# M901X.net
KiCad netlist of a schematic drawn in EAGLE
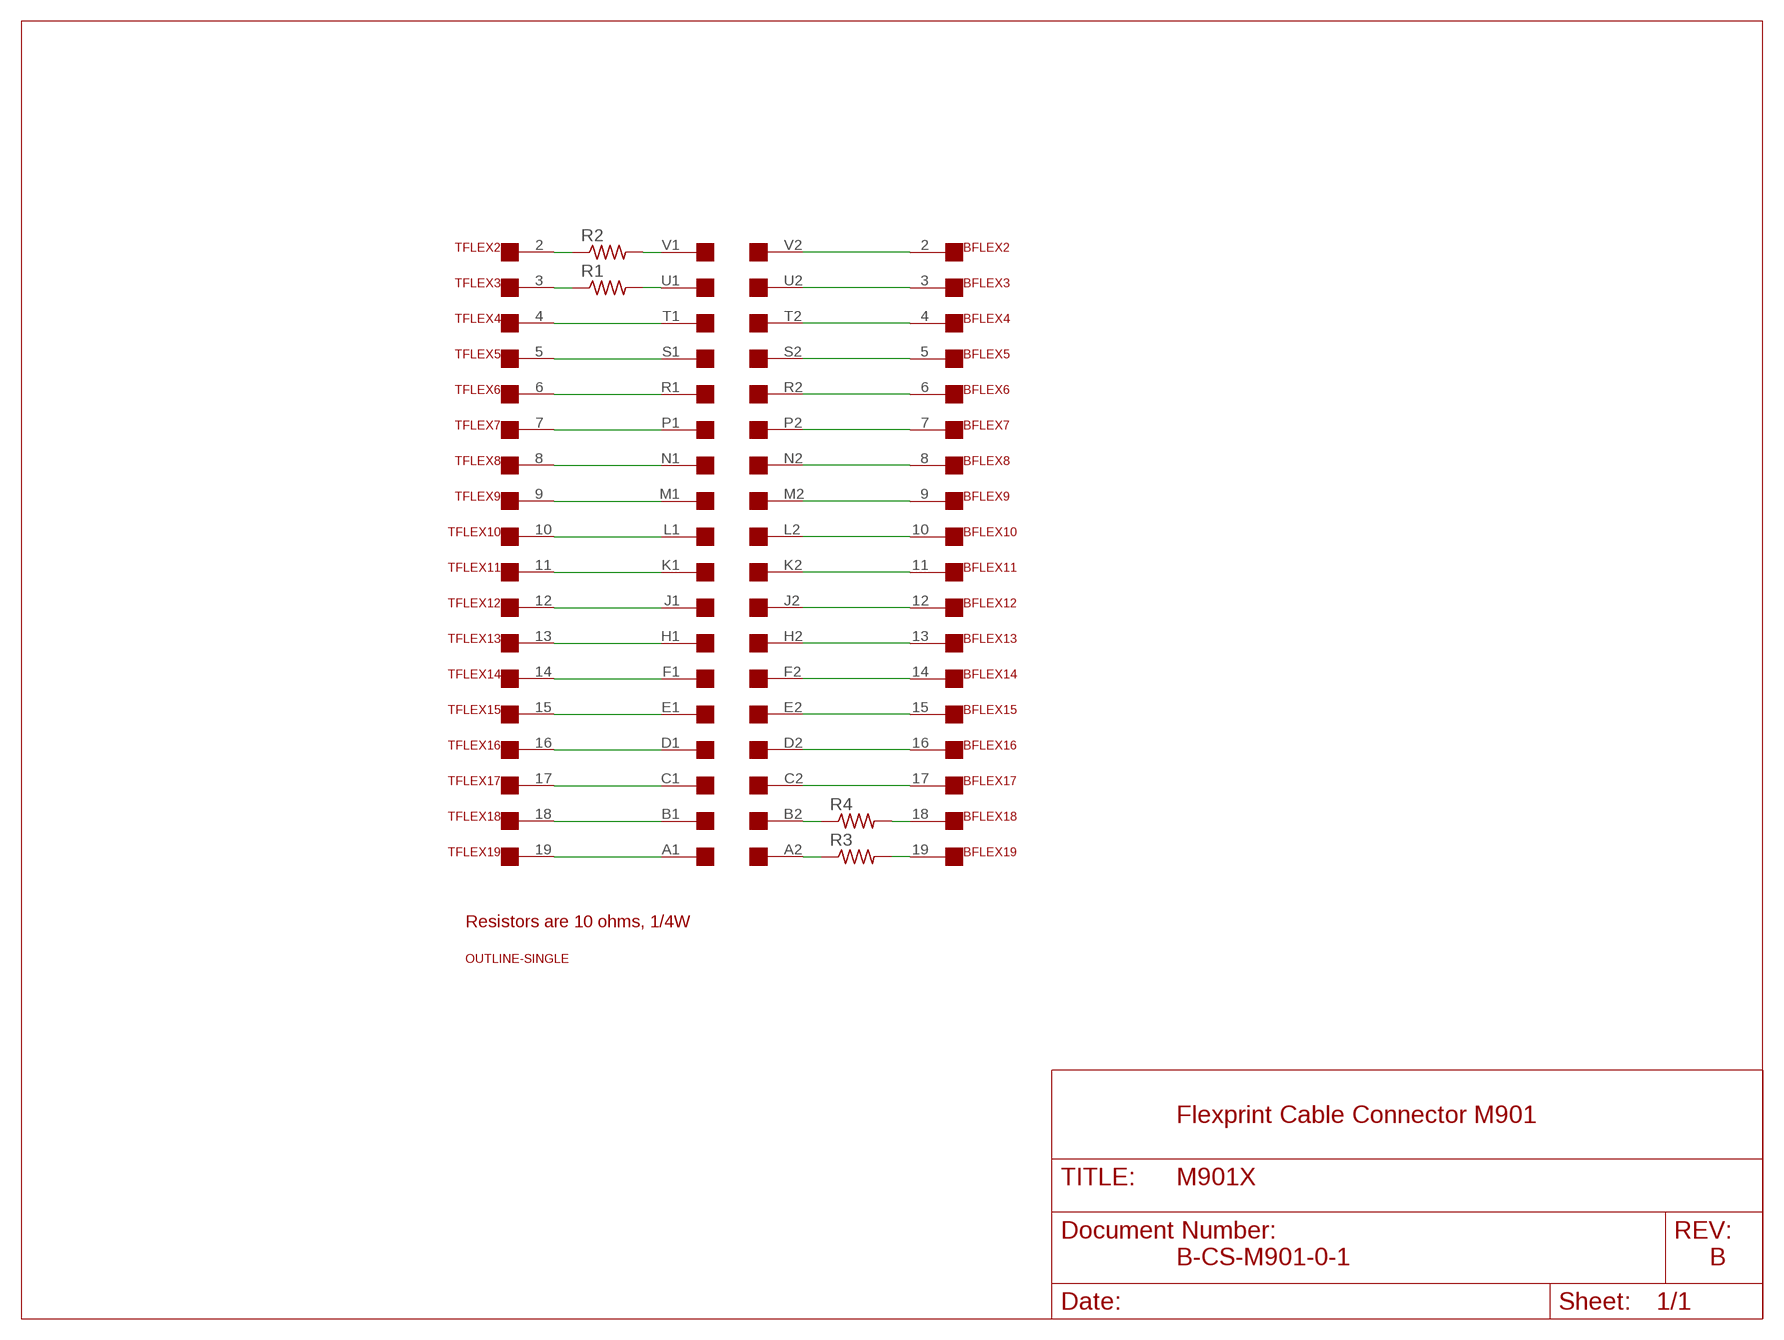
[diagram p0: schematic, sheet 1]

(export (version "E")
  (design (tool "Eeschema 10.0.6"))
  (components
    (comp (ref "BFLEX")
      (value "FLEX19")
      (footprint "eagle-import:FLEX19")
      (libsource (lib "eagle-import") (part "FLEX19"))
    )
    (comp (ref "R1")
      (value "R-US_0207/10")
      (footprint "eagle-import:0207_10")
      (libsource (lib "eagle-import") (part "R-US_0207/10"))
    )
    (comp (ref "R2")
      (value "R-US_0207/10")
      (footprint "eagle-import:0207_10")
      (libsource (lib "eagle-import") (part "R-US_0207/10"))
    )
    (comp (ref "R3")
      (value "R-US_0207/10")
      (footprint "eagle-import:0207_10")
      (libsource (lib "eagle-import") (part "R-US_0207/10"))
    )
    (comp (ref "R4")
      (value "R-US_0207/10")
      (footprint "eagle-import:0207_10")
      (libsource (lib "eagle-import") (part "R-US_0207/10"))
    )
    (comp (ref "TFLEX")
      (value "FLEX19")
      (footprint "eagle-import:FLEX19")
      (libsource (lib "eagle-import") (part "FLEX19"))
    )
    (comp (ref "U$1")
      (value "SINGLE")
      (footprint "eagle-import:EDGE-CON2")
      (libsource (lib "eagle-import") (part "SINGLE"))
    )
    (comp (ref "U$2")
      (value "OUTLINE-SINGLE")
      (footprint "eagle-import:SINGLE")
      (libsource (lib "eagle-import") (part "OUTLINE-SINGLE"))
    )
  )
  (nets
    (net (code "1") (name "Net-(BFLEXB-1)") (class "Default")
      (node (ref "BFLEX") (pin "10") (pinfunction "1_10") (pintype "passive"))
      (node (ref "U$1") (pin "L2") (pinfunction "1_L2") (pintype "bidirectional"))
    )
    (net (code "2") (name "Net-(BFLEXC-1)") (class "Default")
      (node (ref "BFLEX") (pin "11") (pinfunction "1_11") (pintype "passive"))
      (node (ref "U$1") (pin "K2") (pinfunction "1_K2") (pintype "bidirectional"))
    )
    (net (code "3") (name "Net-(BFLEXD-1)") (class "Default")
      (node (ref "BFLEX") (pin "12") (pinfunction "1_12") (pintype "passive"))
      (node (ref "U$1") (pin "J2") (pinfunction "1_J2") (pintype "bidirectional"))
    )
    (net (code "4") (name "Net-(BFLEXE-1)") (class "Default")
      (node (ref "BFLEX") (pin "13") (pinfunction "1_13") (pintype "passive"))
      (node (ref "U$1") (pin "H2") (pinfunction "1_H2") (pintype "bidirectional"))
    )
    (net (code "5") (name "Net-(BFLEXF-1)") (class "Default")
      (node (ref "BFLEX") (pin "14") (pinfunction "1_14") (pintype "passive"))
      (node (ref "U$1") (pin "F2") (pinfunction "1_F2") (pintype "bidirectional"))
    )
    (net (code "6") (name "Net-(BFLEXG-1)") (class "Default")
      (node (ref "BFLEX") (pin "15") (pinfunction "1_15") (pintype "passive"))
      (node (ref "U$1") (pin "E2") (pinfunction "1_E2") (pintype "bidirectional"))
    )
    (net (code "7") (name "Net-(BFLEXH-1)") (class "Default")
      (node (ref "BFLEX") (pin "16") (pinfunction "1_16") (pintype "passive"))
      (node (ref "U$1") (pin "D2") (pinfunction "1_D2") (pintype "bidirectional"))
    )
    (net (code "8") (name "Net-(BFLEXI-1)") (class "Default")
      (node (ref "BFLEX") (pin "17") (pinfunction "1_17") (pintype "passive"))
      (node (ref "U$1") (pin "C2") (pinfunction "1_C2") (pintype "bidirectional"))
    )
    (net (code "9") (name "Net-(BFLEXJ-1)") (class "Default")
      (node (ref "BFLEX") (pin "18") (pinfunction "1_18") (pintype "passive"))
      (node (ref "R4") (pin "2") (pinfunction "2_2") (pintype "passive"))
    )
    (net (code "10") (name "Net-(BFLEXK-1)") (class "Default")
      (node (ref "BFLEX") (pin "19") (pinfunction "1_19") (pintype "passive"))
      (node (ref "R3") (pin "2") (pinfunction "2_2") (pintype "passive"))
    )
    (net (code "11") (name "Net-(BFLEXL-1)") (class "Default")
      (node (ref "BFLEX") (pin "2") (pinfunction "1_2") (pintype "passive"))
      (node (ref "U$1") (pin "V2") (pinfunction "1_V2") (pintype "bidirectional"))
    )
    (net (code "12") (name "Net-(BFLEXM-1)") (class "Default")
      (node (ref "BFLEX") (pin "3") (pinfunction "1_3") (pintype "passive"))
      (node (ref "U$1") (pin "U2") (pinfunction "1_U2") (pintype "bidirectional"))
    )
    (net (code "13") (name "Net-(BFLEXN-1)") (class "Default")
      (node (ref "BFLEX") (pin "4") (pinfunction "1_4") (pintype "passive"))
      (node (ref "U$1") (pin "T2") (pinfunction "1_T2") (pintype "bidirectional"))
    )
    (net (code "14") (name "Net-(BFLEXO-1)") (class "Default")
      (node (ref "BFLEX") (pin "5") (pinfunction "1_5") (pintype "passive"))
      (node (ref "U$1") (pin "S2") (pinfunction "1_S2") (pintype "bidirectional"))
    )
    (net (code "15") (name "Net-(BFLEXP-1)") (class "Default")
      (node (ref "BFLEX") (pin "6") (pinfunction "1_6") (pintype "passive"))
      (node (ref "U$1") (pin "R2") (pinfunction "1_R2") (pintype "bidirectional"))
    )
    (net (code "16") (name "Net-(BFLEXQ-1)") (class "Default")
      (node (ref "BFLEX") (pin "7") (pinfunction "1_7") (pintype "passive"))
      (node (ref "U$1") (pin "P2") (pinfunction "1_P2") (pintype "bidirectional"))
    )
    (net (code "17") (name "Net-(BFLEXR-1)") (class "Default")
      (node (ref "BFLEX") (pin "8") (pinfunction "1_8") (pintype "passive"))
      (node (ref "U$1") (pin "N2") (pinfunction "1_N2") (pintype "bidirectional"))
    )
    (net (code "18") (name "Net-(BFLEXS-1)") (class "Default")
      (node (ref "BFLEX") (pin "9") (pinfunction "1_9") (pintype "passive"))
      (node (ref "U$1") (pin "M2") (pinfunction "1_M2") (pintype "bidirectional"))
    )
    (net (code "19") (name "Net-(TFLEXB-1)") (class "Default")
      (node (ref "TFLEX") (pin "10") (pinfunction "1_10") (pintype "passive"))
      (node (ref "U$1") (pin "L1") (pinfunction "1_L1") (pintype "bidirectional"))
    )
    (net (code "20") (name "Net-(TFLEXC-1)") (class "Default")
      (node (ref "TFLEX") (pin "11") (pinfunction "1_11") (pintype "passive"))
      (node (ref "U$1") (pin "K1") (pinfunction "1_K1") (pintype "bidirectional"))
    )
    (net (code "21") (name "Net-(TFLEXD-1)") (class "Default")
      (node (ref "TFLEX") (pin "12") (pinfunction "1_12") (pintype "passive"))
      (node (ref "U$1") (pin "J1") (pinfunction "1_J1") (pintype "bidirectional"))
    )
    (net (code "22") (name "Net-(TFLEXE-1)") (class "Default")
      (node (ref "TFLEX") (pin "13") (pinfunction "1_13") (pintype "passive"))
      (node (ref "U$1") (pin "H1") (pinfunction "1_H1") (pintype "bidirectional"))
    )
    (net (code "23") (name "Net-(TFLEXF-1)") (class "Default")
      (node (ref "TFLEX") (pin "14") (pinfunction "1_14") (pintype "passive"))
      (node (ref "U$1") (pin "F1") (pinfunction "1_F1") (pintype "bidirectional"))
    )
    (net (code "24") (name "Net-(TFLEXG-1)") (class "Default")
      (node (ref "TFLEX") (pin "15") (pinfunction "1_15") (pintype "passive"))
      (node (ref "U$1") (pin "E1") (pinfunction "1_E1") (pintype "bidirectional"))
    )
    (net (code "25") (name "Net-(TFLEXH-1)") (class "Default")
      (node (ref "TFLEX") (pin "16") (pinfunction "1_16") (pintype "passive"))
      (node (ref "U$1") (pin "D1") (pinfunction "1_D1") (pintype "bidirectional"))
    )
    (net (code "26") (name "Net-(TFLEXI-1)") (class "Default")
      (node (ref "TFLEX") (pin "17") (pinfunction "1_17") (pintype "passive"))
      (node (ref "U$1") (pin "C1") (pinfunction "1_C1") (pintype "bidirectional"))
    )
    (net (code "27") (name "Net-(TFLEXJ-1)") (class "Default")
      (node (ref "TFLEX") (pin "18") (pinfunction "1_18") (pintype "passive"))
      (node (ref "U$1") (pin "B1") (pinfunction "1_B1") (pintype "bidirectional"))
    )
    (net (code "28") (name "Net-(TFLEXK-1)") (class "Default")
      (node (ref "TFLEX") (pin "19") (pinfunction "1_19") (pintype "passive"))
      (node (ref "U$1") (pin "A1") (pinfunction "1_A1") (pintype "bidirectional"))
    )
    (net (code "29") (name "Net-(TFLEXL-1)") (class "Default")
      (node (ref "R2") (pin "1") (pinfunction "1_1") (pintype "passive"))
      (node (ref "TFLEX") (pin "2") (pinfunction "1_2") (pintype "passive"))
    )
    (net (code "30") (name "Net-(TFLEXM-1)") (class "Default")
      (node (ref "R1") (pin "1") (pinfunction "1_1") (pintype "passive"))
      (node (ref "TFLEX") (pin "3") (pinfunction "1_3") (pintype "passive"))
    )
    (net (code "31") (name "Net-(TFLEXN-1)") (class "Default")
      (node (ref "TFLEX") (pin "4") (pinfunction "1_4") (pintype "passive"))
      (node (ref "U$1") (pin "T1") (pinfunction "1_T1") (pintype "bidirectional"))
    )
    (net (code "32") (name "Net-(TFLEXO-1)") (class "Default")
      (node (ref "TFLEX") (pin "5") (pinfunction "1_5") (pintype "passive"))
      (node (ref "U$1") (pin "S1") (pinfunction "1_S1") (pintype "bidirectional"))
    )
    (net (code "33") (name "Net-(TFLEXP-1)") (class "Default")
      (node (ref "TFLEX") (pin "6") (pinfunction "1_6") (pintype "passive"))
      (node (ref "U$1") (pin "R1") (pinfunction "1_R1") (pintype "bidirectional"))
    )
    (net (code "34") (name "Net-(TFLEXQ-1)") (class "Default")
      (node (ref "TFLEX") (pin "7") (pinfunction "1_7") (pintype "passive"))
      (node (ref "U$1") (pin "P1") (pinfunction "1_P1") (pintype "bidirectional"))
    )
    (net (code "35") (name "Net-(TFLEXR-1)") (class "Default")
      (node (ref "TFLEX") (pin "8") (pinfunction "1_8") (pintype "passive"))
      (node (ref "U$1") (pin "N1") (pinfunction "1_N1") (pintype "bidirectional"))
    )
    (net (code "36") (name "Net-(TFLEXS-1)") (class "Default")
      (node (ref "TFLEX") (pin "9") (pinfunction "1_9") (pintype "passive"))
      (node (ref "U$1") (pin "M1") (pinfunction "1_M1") (pintype "bidirectional"))
    )
    (net (code "37") (name "Net-(U$1AG-1)") (class "Default")
      (node (ref "R1") (pin "2") (pinfunction "2_2") (pintype "passive"))
      (node (ref "U$1") (pin "U1") (pinfunction "1_U1") (pintype "bidirectional"))
    )
    (net (code "38") (name "Net-(U$1AI-1)") (class "Default")
      (node (ref "R2") (pin "2") (pinfunction "2_2") (pintype "passive"))
      (node (ref "U$1") (pin "V1") (pinfunction "1_V1") (pintype "bidirectional"))
    )
    (net (code "39") (name "Net-(U$1B-1)") (class "Default")
      (node (ref "R3") (pin "1") (pinfunction "1_1") (pintype "passive"))
      (node (ref "U$1") (pin "A2") (pinfunction "1_A2") (pintype "bidirectional"))
    )
    (net (code "40") (name "Net-(U$1D-1)") (class "Default")
      (node (ref "R4") (pin "1") (pinfunction "1_1") (pintype "passive"))
      (node (ref "U$1") (pin "B2") (pinfunction "1_B2") (pintype "bidirectional"))
    )
  )
)
